# Power_Supply.net
KiCad netlist of a schematic drawn in EAGLE
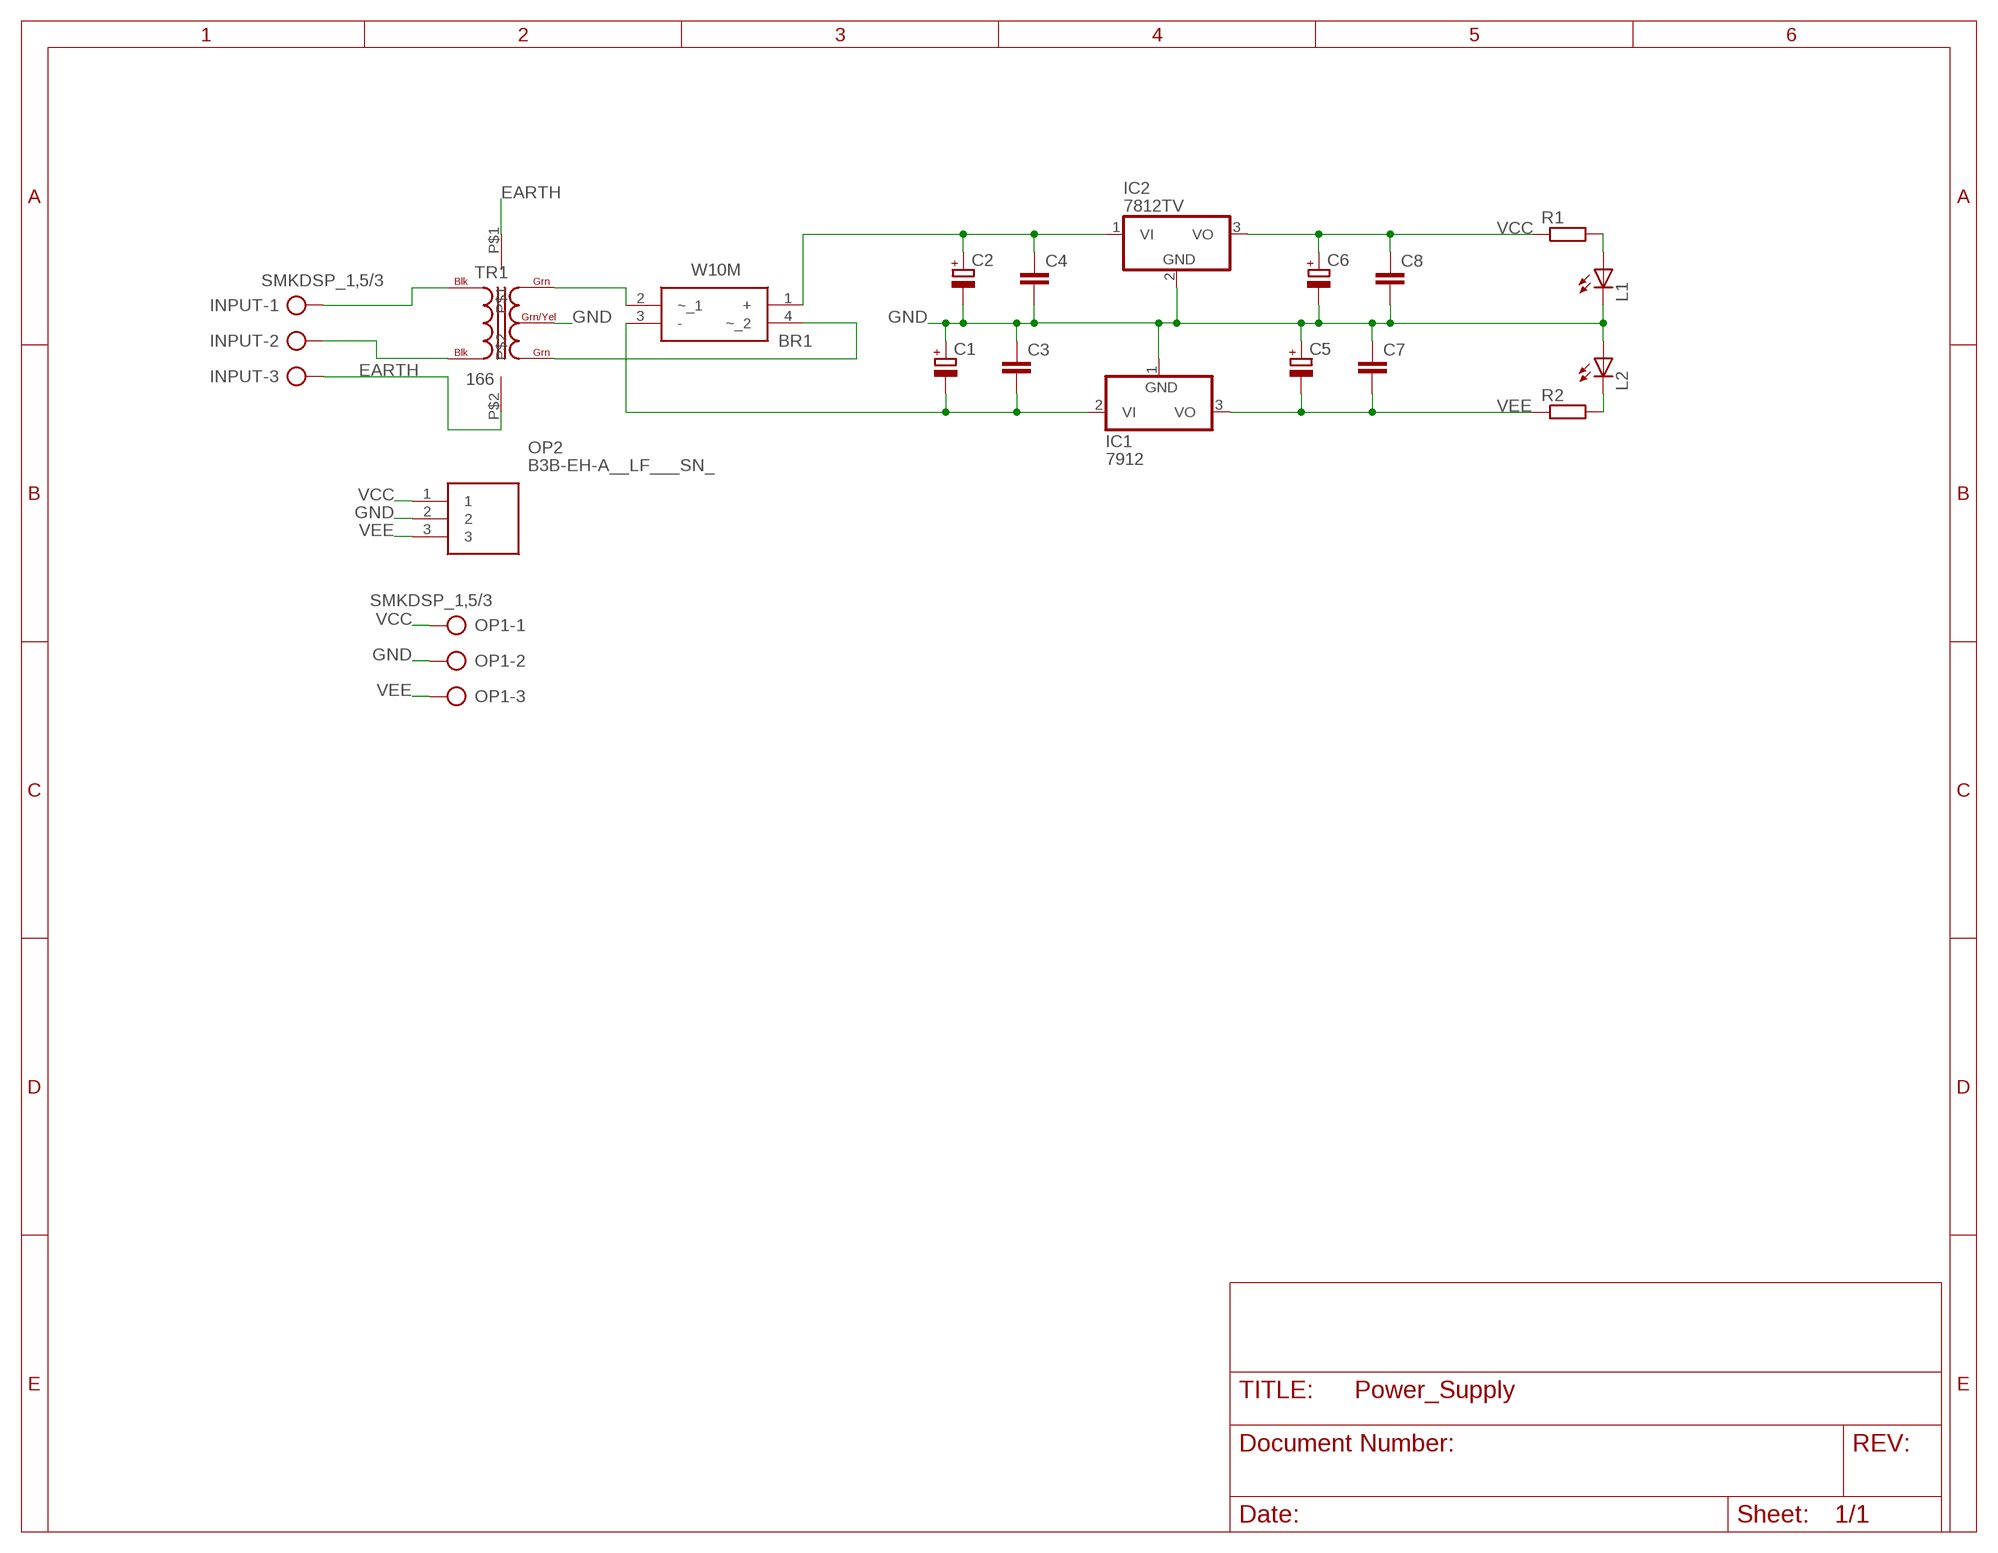
[diagram p0: schematic, sheet 1]

(export (version "E")
  (design (tool "Eeschema 10.0.6"))
  (components
    (comp (ref "BR1")
      (value "W10M")
      (footprint "eagle-import:WOM")
      (fields (field (name "MOUSER_PART_NUMBER") "583-W10M"))
      (libsource (lib "eagle-import") (part "W10M"))
    )
    (comp (ref "C1")
      (value "CPOL-EUE5-10.5")
      (footprint "eagle-import:E5-10,5")
      (libsource (lib "eagle-import") (part "CPOL-EUE5-10.5"))
    )
    (comp (ref "C2")
      (value "CPOL-EUE5-10.5")
      (footprint "eagle-import:E5-10,5")
      (libsource (lib "eagle-import") (part "CPOL-EUE5-10.5"))
    )
    (comp (ref "C3")
      (value "C-EU025-025X050")
      (footprint "eagle-import:C025-025X050")
      (libsource (lib "eagle-import") (part "C-EU025-025X050"))
    )
    (comp (ref "C4")
      (value "C-EU025-025X050")
      (footprint "eagle-import:C025-025X050")
      (libsource (lib "eagle-import") (part "C-EU025-025X050"))
    )
    (comp (ref "C5")
      (value "CPOL-EUE2.5-5")
      (footprint "eagle-import:E2,5-5")
      (libsource (lib "eagle-import") (part "CPOL-EUE2.5-5"))
    )
    (comp (ref "C6")
      (value "CPOL-EUE2.5-5")
      (footprint "eagle-import:E2,5-5")
      (libsource (lib "eagle-import") (part "CPOL-EUE2.5-5"))
    )
    (comp (ref "C7")
      (value "C-EU025-025X050")
      (footprint "eagle-import:C025-025X050")
      (libsource (lib "eagle-import") (part "C-EU025-025X050"))
    )
    (comp (ref "C8")
      (value "C-EU025-025X050")
      (footprint "eagle-import:C025-025X050")
      (libsource (lib "eagle-import") (part "C-EU025-025X050"))
    )
    (comp (ref "IC1")
      (value "7912")
      (footprint "eagle-import:TO220V")
      (libsource (lib "eagle-import") (part "79"))
    )
    (comp (ref "IC2")
      (value "7812TV")
      (footprint "eagle-import:TO220V")
      (libsource (lib "eagle-import") (part "78TV12"))
    )
    (comp (ref "INPUT")
      (value "SMKDSP_1,5/3")
      (footprint "eagle-import:SMKDSP_1,5_3")
      (fields (field (name "MF") "FARNELL") (field (name "MPN") "1733583"))
      (libsource (lib "eagle-import") (part "SMKDSP_1,5/3"))
    )
    (comp (ref "L1")
      (value "LED3MM")
      (footprint "eagle-import:LED3MM")
      (libsource (lib "eagle-import") (part "LED3MM"))
    )
    (comp (ref "L2")
      (value "LED3MM")
      (footprint "eagle-import:LED3MM")
      (libsource (lib "eagle-import") (part "LED3MM"))
    )
    (comp (ref "OP1")
      (value "SMKDSP_1,5/3")
      (footprint "eagle-import:SMKDSP_1,5_3")
      (fields (field (name "MF") "FARNELL") (field (name "MPN") "1733583"))
      (libsource (lib "eagle-import") (part "SMKDSP_1,5/3"))
    )
    (comp (ref "OP2")
      (value "B3B-EH-A__LF___SN_")
      (footprint "eagle-import:SHDR3W64P0X250_1X3_1000X380X60")
      (fields (field (name "ARROW_PART_NUMBER") "B3B-EH-A (LF) (SN)"))
      (libsource (lib "eagle-import") (part "B3B-EH-A__LF___SN_"))
    )
    (comp (ref "R1")
      (value "R-EU_0207/10")
      (footprint "eagle-import:0207_10")
      (libsource (lib "eagle-import") (part "R-EU_0207/10"))
    )
    (comp (ref "R2")
      (value "R-EU_0207/10")
      (footprint "eagle-import:0207_10")
      (libsource (lib "eagle-import") (part "R-EU_0207/10"))
    )
    (comp (ref "TR1")
      (value "166")
      (footprint "eagle-import:C4H")
      (libsource (lib "eagle-import") (part "166"))
    )
  )
  (nets
    (net (code "1") (name "/EARTH") (class "Default")
      (node (ref "INPUT") (pin "3") (pinfunction "KL_3") (pintype "passive"))
      (node (ref "TR1") (pin "P$1") (pinfunction "P$1_P$1") (pintype "bidirectional"))
      (node (ref "TR1") (pin "P$2") (pinfunction "P$2_P$2") (pintype "bidirectional"))
    )
    (net (code "2") (name "/GND") (class "Default")
      (node (ref "C1") (pin "+") (pinfunction "+_+") (pintype "passive"))
      (node (ref "C2") (pin "-") (pinfunction "-_-") (pintype "passive"))
      (node (ref "C3") (pin "1") (pinfunction "1_1") (pintype "passive"))
      (node (ref "C4") (pin "2") (pinfunction "2_2") (pintype "passive"))
      (node (ref "C5") (pin "+") (pinfunction "+_+") (pintype "passive"))
      (node (ref "C6") (pin "-") (pinfunction "-_-") (pintype "passive"))
      (node (ref "C7") (pin "1") (pinfunction "1_1") (pintype "passive"))
      (node (ref "C8") (pin "2") (pinfunction "2_2") (pintype "passive"))
      (node (ref "IC1") (pin "1") (pinfunction "GND_1") (pintype "passive"))
      (node (ref "IC2") (pin "2") (pinfunction "GND_2") (pintype "passive"))
      (node (ref "L1") (pin "K") (pinfunction "C_K") (pintype "passive"))
      (node (ref "L2") (pin "A") (pinfunction "A_A") (pintype "passive"))
      (node (ref "OP1") (pin "2") (pinfunction "KL_2") (pintype "passive"))
      (node (ref "OP2") (pin "2") (pinfunction "2_2") (pintype "bidirectional"))
      (node (ref "TR1") (pin "GRN/YEL") (pinfunction "GRN/YEL_GRN/YEL") (pintype "passive"))
    )
    (net (code "3") (name "/VCC") (class "Default")
      (node (ref "C6") (pin "+") (pinfunction "+_+") (pintype "passive"))
      (node (ref "C8") (pin "1") (pinfunction "1_1") (pintype "passive"))
      (node (ref "IC2") (pin "3") (pinfunction "VO_3") (pintype "passive"))
      (node (ref "OP1") (pin "1") (pinfunction "KL_1") (pintype "passive"))
      (node (ref "OP2") (pin "1") (pinfunction "1_1") (pintype "bidirectional"))
      (node (ref "R1") (pin "1") (pinfunction "1_1") (pintype "passive"))
    )
    (net (code "4") (name "/VEE") (class "Default")
      (node (ref "C5") (pin "-") (pinfunction "-_-") (pintype "passive"))
      (node (ref "C7") (pin "2") (pinfunction "2_2") (pintype "passive"))
      (node (ref "IC1") (pin "3") (pinfunction "VO_3") (pintype "passive"))
      (node (ref "OP1") (pin "3") (pinfunction "KL_3") (pintype "passive"))
      (node (ref "OP2") (pin "3") (pinfunction "3_3") (pintype "bidirectional"))
      (node (ref "R2") (pin "1") (pinfunction "1_1") (pintype "passive"))
    )
    (net (code "5") (name "Net-(BR1-+)") (class "Default")
      (node (ref "BR1") (pin "1") (pinfunction "+_1") (pintype "bidirectional"))
      (node (ref "C2") (pin "+") (pinfunction "+_+") (pintype "passive"))
      (node (ref "C4") (pin "1") (pinfunction "1_1") (pintype "passive"))
      (node (ref "IC2") (pin "1") (pinfunction "VI_1") (pintype "input"))
    )
    (net (code "6") (name "Net-(BR1--)") (class "Default")
      (node (ref "BR1") (pin "3") (pinfunction "-_3") (pintype "bidirectional"))
      (node (ref "C1") (pin "-") (pinfunction "-_-") (pintype "passive"))
      (node (ref "C3") (pin "2") (pinfunction "2_2") (pintype "passive"))
      (node (ref "IC1") (pin "2") (pinfunction "VI_2") (pintype "input"))
    )
    (net (code "7") (name "Net-(BR1-~{_1})") (class "Default")
      (node (ref "BR1") (pin "2") (pinfunction "~{_1}_2") (pintype "bidirectional"))
      (node (ref "TR1") (pin "GRN@1") (pinfunction "GRN_GRN@1") (pintype "passive"))
    )
    (net (code "8") (name "Net-(BR1-~{_2})") (class "Default")
      (node (ref "BR1") (pin "4") (pinfunction "~{_2}_4") (pintype "bidirectional"))
      (node (ref "TR1") (pin "GRN@2") (pinfunction "GRN_GRN@2") (pintype "passive"))
    )
    (net (code "9") (name "Net-(INPUTA-KL)") (class "Default")
      (node (ref "INPUT") (pin "1") (pinfunction "KL_1") (pintype "passive"))
      (node (ref "TR1") (pin "BLK@1") (pinfunction "BLK_BLK@1") (pintype "passive"))
    )
    (net (code "10") (name "Net-(INPUTB-KL)") (class "Default")
      (node (ref "INPUT") (pin "2") (pinfunction "KL_2") (pintype "passive"))
      (node (ref "TR1") (pin "BLK@2") (pinfunction "BLK_BLK@2") (pintype "passive"))
    )
    (net (code "11") (name "Net-(L1-PadA)") (class "Default")
      (node (ref "L1") (pin "A") (pinfunction "A_A") (pintype "passive"))
      (node (ref "R1") (pin "2") (pinfunction "2_2") (pintype "passive"))
    )
    (net (code "12") (name "Net-(L2-C)") (class "Default")
      (node (ref "L2") (pin "K") (pinfunction "C_K") (pintype "passive"))
      (node (ref "R2") (pin "2") (pinfunction "2_2") (pintype "passive"))
    )
  )
)
